# IN-12.net
KiCad netlist of a schematic drawn in EAGLE
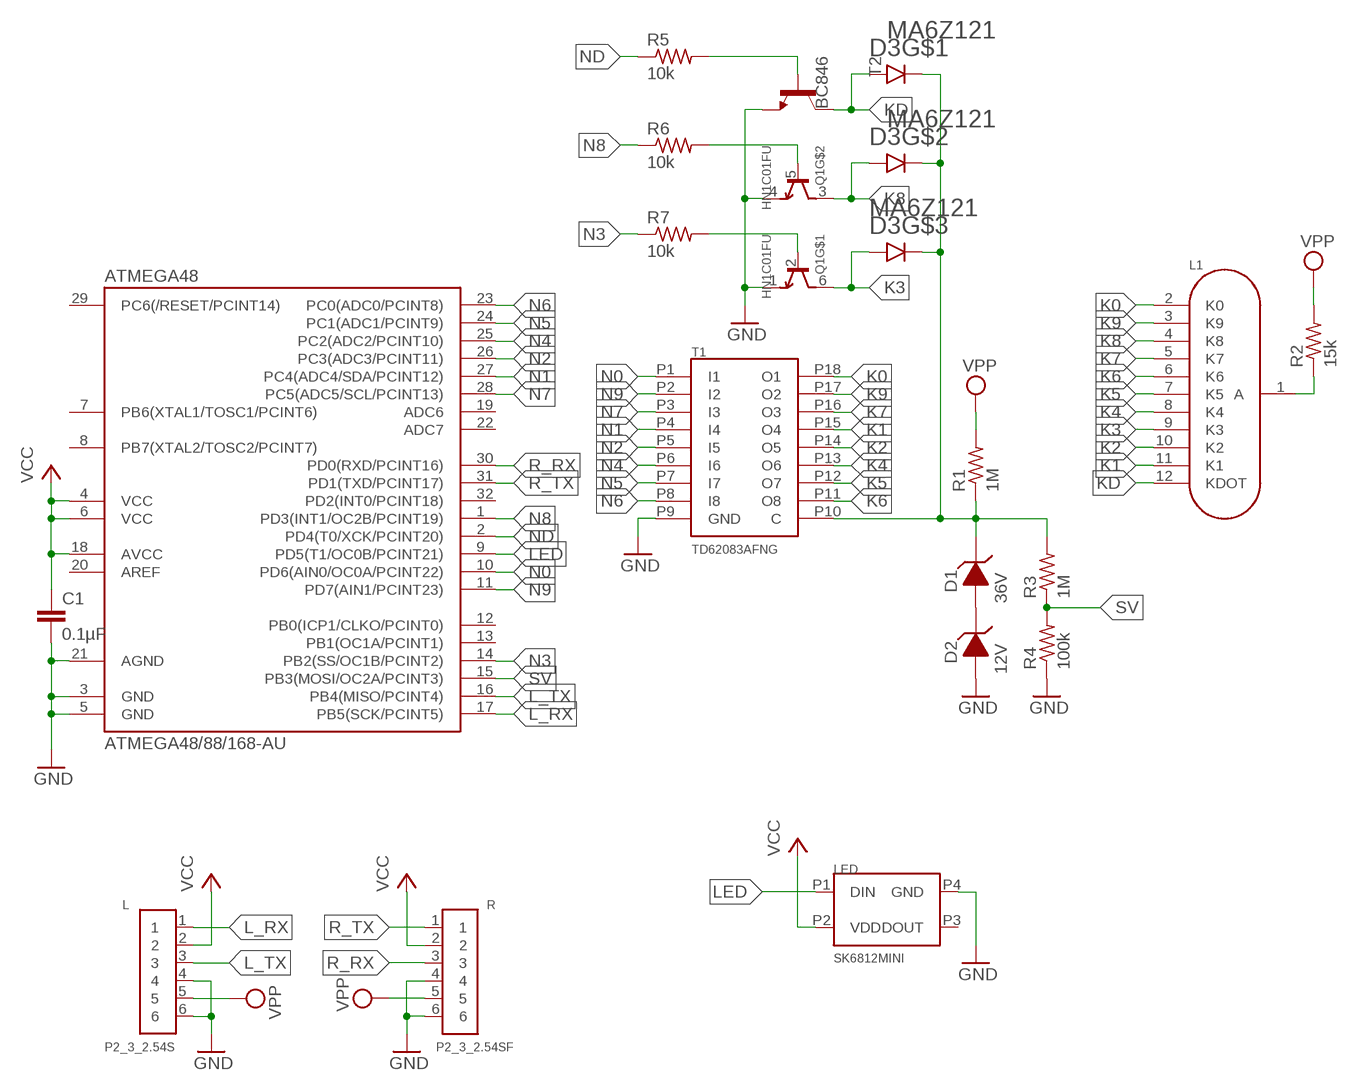
[diagram p0: schematic, sheet 1]

(export (version "E")
  (design (tool "Eeschema 10.0.6"))
  (components
    (comp (ref "ATMEGA48")
      (value "ATMEGA48/88/168-AU")
      (footprint "eagle-import:TQFP32-08")
      (libsource (lib "eagle-import") (part "ATMEGA48/88/168-AU"))
    )
    (comp (ref "C1")
      (value "0.1µF")
      (footprint "eagle-import:C0603")
      (libsource (lib "eagle-import") (part "C-EUC0603"))
    )
    (comp (ref "D1")
      (value "36V")
      (footprint "eagle-import:S-MINI-2P")
      (libsource (lib "eagle-import") (part "D_ZENERG"))
    )
    (comp (ref "D2")
      (value "12V")
      (footprint "eagle-import:S-MINI-2P")
      (libsource (lib "eagle-import") (part "D_ZENERG"))
    )
    (comp (ref "D3")
      (value "MA6Z121")
      (footprint "eagle-import:SMINI6-F1")
      (libsource (lib "eagle-import") (part "MA6Z121"))
    )
    (comp (ref "L")
      (value "P2_3_2.54S")
      (footprint "eagle-import:P2_3_2.54S")
      (libsource (lib "eagle-import") (part "P2_3_2.54S"))
    )
    (comp (ref "L1")
      (value "IN-12B_PS")
      (footprint "eagle-import:IN-12_PS")
      (libsource (lib "eagle-import") (part "IN-12B_PS"))
    )
    (comp (ref "LED")
      (value "SK6812MINI")
      (footprint "eagle-import:SK68XXMINI")
      (libsource (lib "eagle-import") (part "SK6812MINI"))
    )
    (comp (ref "Q1")
      (value "HN1C01FU")
      (footprint "eagle-import:SOT-363")
      (libsource (lib "eagle-import") (part "HN1C01FU"))
    )
    (comp (ref "R")
      (value "P2_3_2.54SF")
      (footprint "eagle-import:P2_3_2.54SF")
      (libsource (lib "eagle-import") (part "P2_3_2.54SF"))
    )
    (comp (ref "R1")
      (value "1M")
      (footprint "eagle-import:R0603")
      (libsource (lib "eagle-import") (part "R-US_R0603"))
    )
    (comp (ref "R2")
      (value "15k")
      (footprint "eagle-import:R1206")
      (libsource (lib "eagle-import") (part "R-US_R1206"))
    )
    (comp (ref "R3")
      (value "1M")
      (footprint "eagle-import:R0603")
      (libsource (lib "eagle-import") (part "R-US_R0603"))
    )
    (comp (ref "R4")
      (value "100k")
      (footprint "eagle-import:R0603")
      (libsource (lib "eagle-import") (part "R-US_R0603"))
    )
    (comp (ref "R5")
      (value "10k")
      (footprint "eagle-import:R0603")
      (libsource (lib "eagle-import") (part "R-US_R0603"))
    )
    (comp (ref "R6")
      (value "10k")
      (footprint "eagle-import:R0603")
      (libsource (lib "eagle-import") (part "R-US_R0603"))
    )
    (comp (ref "R7")
      (value "10k")
      (footprint "eagle-import:R0603")
      (libsource (lib "eagle-import") (part "R-US_R0603"))
    )
    (comp (ref "T1")
      (value "TD62083AFNG")
      (footprint "eagle-import:SSOP18-P-225-0.65")
      (libsource (lib "eagle-import") (part "TD62083AFNG"))
    )
    (comp (ref "T2")
      (value "BC846")
      (footprint "eagle-import:SOT23")
      (libsource (lib "eagle-import") (part "BC846"))
    )
  )
  (nets
    (net (code "1") (name "GND") (class "Default")
      (node (ref "ATMEGA48") (pin "21") (pinfunction "AGND_21") (pintype "power_in"))
      (node (ref "ATMEGA48") (pin "3") (pinfunction "GND_3") (pintype "power_in"))
      (node (ref "ATMEGA48") (pin "5") (pinfunction "GND_5") (pintype "power_in"))
      (node (ref "C1") (pin "2") (pinfunction "2_2") (pintype "passive"))
      (node (ref "D2") (pin "1") (pinfunction "A_1") (pintype "passive"))
      (node (ref "L") (pin "4") (pinfunction "4_4") (pintype "bidirectional"))
      (node (ref "L") (pin "6") (pinfunction "6_6") (pintype "bidirectional"))
      (node (ref "LED") (pin "P4") (pinfunction "GND_P4") (pintype "bidirectional"))
      (node (ref "Q1") (pin "1") (pinfunction "E_1") (pintype "bidirectional"))
      (node (ref "Q1") (pin "4") (pinfunction "E_4") (pintype "bidirectional"))
      (node (ref "R") (pin "4") (pinfunction "4_4") (pintype "bidirectional"))
      (node (ref "R") (pin "6") (pinfunction "6_6") (pintype "bidirectional"))
      (node (ref "R4") (pin "1") (pinfunction "1_1") (pintype "passive"))
      (node (ref "T1") (pin "P9") (pinfunction "GND_P9") (pintype "power_in"))
      (node (ref "T2") (pin "2") (pinfunction "E_2") (pintype "passive"))
    )
    (net (code "2") (name "K0") (class "Default")
      (node (ref "L1") (pin "2") (pinfunction "K0_2") (pintype "bidirectional"))
      (node (ref "T1") (pin "P18") (pinfunction "O1_P18") (pintype "bidirectional"))
    )
    (net (code "3") (name "K1") (class "Default")
      (node (ref "L1") (pin "11") (pinfunction "K1_11") (pintype "bidirectional"))
      (node (ref "T1") (pin "P15") (pinfunction "O4_P15") (pintype "bidirectional"))
    )
    (net (code "4") (name "K2") (class "Default")
      (node (ref "L1") (pin "10") (pinfunction "K2_10") (pintype "bidirectional"))
      (node (ref "T1") (pin "P14") (pinfunction "O5_P14") (pintype "bidirectional"))
    )
    (net (code "5") (name "K3") (class "Default")
      (node (ref "D3") (pin "P3") (pinfunction "A_P3") (pintype "bidirectional"))
      (node (ref "L1") (pin "9") (pinfunction "K3_9") (pintype "bidirectional"))
      (node (ref "Q1") (pin "6") (pinfunction "C_6") (pintype "bidirectional"))
    )
    (net (code "6") (name "K4") (class "Default")
      (node (ref "L1") (pin "8") (pinfunction "K4_8") (pintype "bidirectional"))
      (node (ref "T1") (pin "P13") (pinfunction "O6_P13") (pintype "bidirectional"))
    )
    (net (code "7") (name "K5") (class "Default")
      (node (ref "L1") (pin "7") (pinfunction "K5_7") (pintype "bidirectional"))
      (node (ref "T1") (pin "P12") (pinfunction "O7_P12") (pintype "bidirectional"))
    )
    (net (code "8") (name "K6") (class "Default")
      (node (ref "L1") (pin "6") (pinfunction "K6_6") (pintype "bidirectional"))
      (node (ref "T1") (pin "P11") (pinfunction "O8_P11") (pintype "bidirectional"))
    )
    (net (code "9") (name "K7") (class "Default")
      (node (ref "L1") (pin "5") (pinfunction "K7_5") (pintype "bidirectional"))
      (node (ref "T1") (pin "P16") (pinfunction "O3_P16") (pintype "bidirectional"))
    )
    (net (code "10") (name "K8") (class "Default")
      (node (ref "D3") (pin "P2") (pinfunction "A_P2") (pintype "bidirectional"))
      (node (ref "L1") (pin "4") (pinfunction "K8_4") (pintype "bidirectional"))
      (node (ref "Q1") (pin "3") (pinfunction "C_3") (pintype "bidirectional"))
    )
    (net (code "11") (name "K9") (class "Default")
      (node (ref "L1") (pin "3") (pinfunction "K9_3") (pintype "bidirectional"))
      (node (ref "T1") (pin "P17") (pinfunction "O2_P17") (pintype "bidirectional"))
    )
    (net (code "12") (name "KD") (class "Default")
      (node (ref "D3") (pin "P1") (pinfunction "A_P1") (pintype "bidirectional"))
      (node (ref "L1") (pin "12") (pinfunction "KDOT_12") (pintype "bidirectional"))
      (node (ref "T2") (pin "3") (pinfunction "C_3") (pintype "passive"))
    )
    (net (code "13") (name "LED") (class "Default")
      (node (ref "ATMEGA48") (pin "9") (pinfunction "PD5(T1/OC0B/PCINT21)_9") (pintype "bidirectional"))
      (node (ref "LED") (pin "P1") (pinfunction "DIN_P1") (pintype "bidirectional"))
    )
    (net (code "14") (name "L_RX") (class "Default")
      (node (ref "ATMEGA48") (pin "17") (pinfunction "PB5(SCK/PCINT5)_17") (pintype "bidirectional"))
      (node (ref "L") (pin "1") (pinfunction "1_1") (pintype "bidirectional"))
    )
    (net (code "15") (name "L_TX") (class "Default")
      (node (ref "ATMEGA48") (pin "16") (pinfunction "PB4(MISO/PCINT4)_16") (pintype "bidirectional"))
      (node (ref "L") (pin "3") (pinfunction "3_3") (pintype "bidirectional"))
    )
    (net (code "16") (name "N0") (class "Default")
      (node (ref "ATMEGA48") (pin "10") (pinfunction "PD6(AIN0/OC0A/PCINT22)_10") (pintype "bidirectional"))
      (node (ref "T1") (pin "P1") (pinfunction "I1_P1") (pintype "input"))
    )
    (net (code "17") (name "N1") (class "Default")
      (node (ref "ATMEGA48") (pin "27") (pinfunction "PC4(ADC4/SDA/PCINT12)_27") (pintype "bidirectional"))
      (node (ref "T1") (pin "P4") (pinfunction "I4_P4") (pintype "input"))
    )
    (net (code "18") (name "N2") (class "Default")
      (node (ref "ATMEGA48") (pin "26") (pinfunction "PC3(ADC3/PCINT11)_26") (pintype "bidirectional"))
      (node (ref "T1") (pin "P5") (pinfunction "I5_P5") (pintype "input"))
    )
    (net (code "19") (name "N3") (class "Default")
      (node (ref "ATMEGA48") (pin "14") (pinfunction "PB2(SS/OC1B/PCINT2)_14") (pintype "bidirectional"))
      (node (ref "R7") (pin "1") (pinfunction "1_1") (pintype "passive"))
    )
    (net (code "20") (name "N4") (class "Default")
      (node (ref "ATMEGA48") (pin "25") (pinfunction "PC2(ADC2/PCINT10)_25") (pintype "bidirectional"))
      (node (ref "T1") (pin "P6") (pinfunction "I6_P6") (pintype "input"))
    )
    (net (code "21") (name "N5") (class "Default")
      (node (ref "ATMEGA48") (pin "24") (pinfunction "PC1(ADC1/PCINT9)_24") (pintype "bidirectional"))
      (node (ref "T1") (pin "P7") (pinfunction "I7_P7") (pintype "input"))
    )
    (net (code "22") (name "N6") (class "Default")
      (node (ref "ATMEGA48") (pin "23") (pinfunction "PC0(ADC0/PCINT8)_23") (pintype "bidirectional"))
      (node (ref "T1") (pin "P8") (pinfunction "I8_P8") (pintype "input"))
    )
    (net (code "23") (name "N7") (class "Default")
      (node (ref "ATMEGA48") (pin "28") (pinfunction "PC5(ADC5/SCL/PCINT13)_28") (pintype "bidirectional"))
      (node (ref "T1") (pin "P3") (pinfunction "I3_P3") (pintype "input"))
    )
    (net (code "24") (name "N8") (class "Default")
      (node (ref "ATMEGA48") (pin "1") (pinfunction "PD3(INT1/OC2B/PCINT19)_1") (pintype "bidirectional"))
      (node (ref "R6") (pin "1") (pinfunction "1_1") (pintype "passive"))
    )
    (net (code "25") (name "N9") (class "Default")
      (node (ref "ATMEGA48") (pin "11") (pinfunction "PD7(AIN1/PCINT23)_11") (pintype "bidirectional"))
      (node (ref "T1") (pin "P2") (pinfunction "I2_P2") (pintype "input"))
    )
    (net (code "26") (name "ND") (class "Default")
      (node (ref "ATMEGA48") (pin "2") (pinfunction "PD4(T0/XCK/PCINT20)_2") (pintype "bidirectional"))
      (node (ref "R5") (pin "1") (pinfunction "1_1") (pintype "passive"))
    )
    (net (code "27") (name "Net-(D1-A)") (class "Default")
      (node (ref "D1") (pin "1") (pinfunction "A_1") (pintype "passive"))
      (node (ref "D2") (pin "2") (pinfunction "C_2") (pintype "passive"))
    )
    (net (code "28") (name "Net-(D1-C)") (class "Default")
      (node (ref "D1") (pin "2") (pinfunction "C_2") (pintype "passive"))
      (node (ref "D3") (pin "P4") (pinfunction "C_P4") (pintype "bidirectional"))
      (node (ref "D3") (pin "P5") (pinfunction "C_P5") (pintype "bidirectional"))
      (node (ref "D3") (pin "P6") (pinfunction "C_P6") (pintype "bidirectional"))
      (node (ref "R1") (pin "1") (pinfunction "1_1") (pintype "passive"))
      (node (ref "R3") (pin "2") (pinfunction "2_2") (pintype "passive"))
      (node (ref "T1") (pin "P10") (pinfunction "C_P10") (pintype "bidirectional"))
    )
    (net (code "29") (name "Net-(L1-A)") (class "Default")
      (node (ref "L1") (pin "1") (pinfunction "A_1") (pintype "bidirectional"))
      (node (ref "R2") (pin "1") (pinfunction "1_1") (pintype "passive"))
    )
    (net (code "30") (name "Net-(Q1A-B)") (class "Default")
      (node (ref "Q1") (pin "2") (pinfunction "B_2") (pintype "bidirectional"))
      (node (ref "R7") (pin "2") (pinfunction "2_2") (pintype "passive"))
    )
    (net (code "31") (name "Net-(Q1B-B)") (class "Default")
      (node (ref "Q1") (pin "5") (pinfunction "B_5") (pintype "bidirectional"))
      (node (ref "R6") (pin "2") (pinfunction "2_2") (pintype "passive"))
    )
    (net (code "32") (name "Net-(T2-B)") (class "Default")
      (node (ref "R5") (pin "2") (pinfunction "2_2") (pintype "passive"))
      (node (ref "T2") (pin "1") (pinfunction "B_1") (pintype "passive"))
    )
    (net (code "33") (name "R_RX") (class "Default")
      (node (ref "ATMEGA48") (pin "30") (pinfunction "PD0(RXD/PCINT16)_30") (pintype "bidirectional"))
      (node (ref "R") (pin "3") (pinfunction "3_3") (pintype "bidirectional"))
    )
    (net (code "34") (name "R_TX") (class "Default")
      (node (ref "ATMEGA48") (pin "31") (pinfunction "PD1(TXD/PCINT17)_31") (pintype "bidirectional"))
      (node (ref "R") (pin "1") (pinfunction "1_1") (pintype "bidirectional"))
    )
    (net (code "35") (name "SV") (class "Default")
      (node (ref "ATMEGA48") (pin "15") (pinfunction "PB3(MOSI/OC2A/PCINT3)_15") (pintype "bidirectional"))
      (node (ref "R3") (pin "1") (pinfunction "1_1") (pintype "passive"))
      (node (ref "R4") (pin "2") (pinfunction "2_2") (pintype "passive"))
    )
    (net (code "36") (name "VCC") (class "Default")
      (node (ref "ATMEGA48") (pin "18") (pinfunction "AVCC_18") (pintype "passive"))
      (node (ref "ATMEGA48") (pin "4") (pinfunction "VCC_4") (pintype "power_in"))
      (node (ref "ATMEGA48") (pin "6") (pinfunction "VCC_6") (pintype "power_in"))
      (node (ref "C1") (pin "1") (pinfunction "1_1") (pintype "passive"))
      (node (ref "L") (pin "2") (pinfunction "2_2") (pintype "bidirectional"))
      (node (ref "LED") (pin "P2") (pinfunction "VDD_P2") (pintype "bidirectional"))
      (node (ref "R") (pin "2") (pinfunction "2_2") (pintype "bidirectional"))
    )
    (net (code "37") (name "VPP") (class "Default")
      (node (ref "L") (pin "5") (pinfunction "5_5") (pintype "bidirectional"))
      (node (ref "R") (pin "5") (pinfunction "5_5") (pintype "bidirectional"))
      (node (ref "R1") (pin "2") (pinfunction "2_2") (pintype "passive"))
      (node (ref "R2") (pin "2") (pinfunction "2_2") (pintype "passive"))
    )
    (net (code "38") (name "unconnected-(ATMEGA48-ADC6-Pad19)") (class "Default")
      (node (ref "ATMEGA48") (pin "19") (pinfunction "ADC6_19") (pintype "passive"))
    )
    (net (code "39") (name "unconnected-(ATMEGA48-ADC7-Pad22)") (class "Default")
      (node (ref "ATMEGA48") (pin "22") (pinfunction "ADC7_22") (pintype "passive"))
    )
    (net (code "40") (name "unconnected-(ATMEGA48-AREF-Pad20)") (class "Default")
      (node (ref "ATMEGA48") (pin "20") (pinfunction "AREF_20") (pintype "passive"))
    )
    (net (code "41") (name "unconnected-(ATMEGA48-PB0(ICP1{slash}CLKO{slash}PCINT0)-Pad12)") (class "Default")
      (node (ref "ATMEGA48") (pin "12") (pinfunction "PB0(ICP1/CLKO/PCINT0)_12") (pintype "bidirectional"))
    )
    (net (code "42") (name "unconnected-(ATMEGA48-PB1(OC1A{slash}PCINT1)-Pad13)") (class "Default")
      (node (ref "ATMEGA48") (pin "13") (pinfunction "PB1(OC1A/PCINT1)_13") (pintype "bidirectional"))
    )
    (net (code "43") (name "unconnected-(ATMEGA48-PB6(XTAL1{slash}TOSC1{slash}PCINT6)-Pad7)") (class "Default")
      (node (ref "ATMEGA48") (pin "7") (pinfunction "PB6(XTAL1/TOSC1/PCINT6)_7") (pintype "bidirectional"))
    )
    (net (code "44") (name "unconnected-(ATMEGA48-PB7(XTAL2{slash}TOSC2{slash}PCINT7)-Pad8)") (class "Default")
      (node (ref "ATMEGA48") (pin "8") (pinfunction "PB7(XTAL2/TOSC2/PCINT7)_8") (pintype "bidirectional"))
    )
    (net (code "45") (name "unconnected-(ATMEGA48-PC6({slash}RESET{slash}PCINT14)-Pad29)") (class "Default")
      (node (ref "ATMEGA48") (pin "29") (pinfunction "PC6(/RESET/PCINT14)_29") (pintype "bidirectional"))
    )
    (net (code "46") (name "unconnected-(ATMEGA48-PD2(INT0{slash}PCINT18)-Pad32)") (class "Default")
      (node (ref "ATMEGA48") (pin "32") (pinfunction "PD2(INT0/PCINT18)_32") (pintype "bidirectional"))
    )
    (net (code "47") (name "unconnected-(LED-DOUT-PadP3)") (class "Default")
      (node (ref "LED") (pin "P3") (pinfunction "DOUT_P3") (pintype "bidirectional"))
    )
  )
)
